# design_1_-_fan_controller.net
KiCad netlist of a schematic drawn in EAGLE
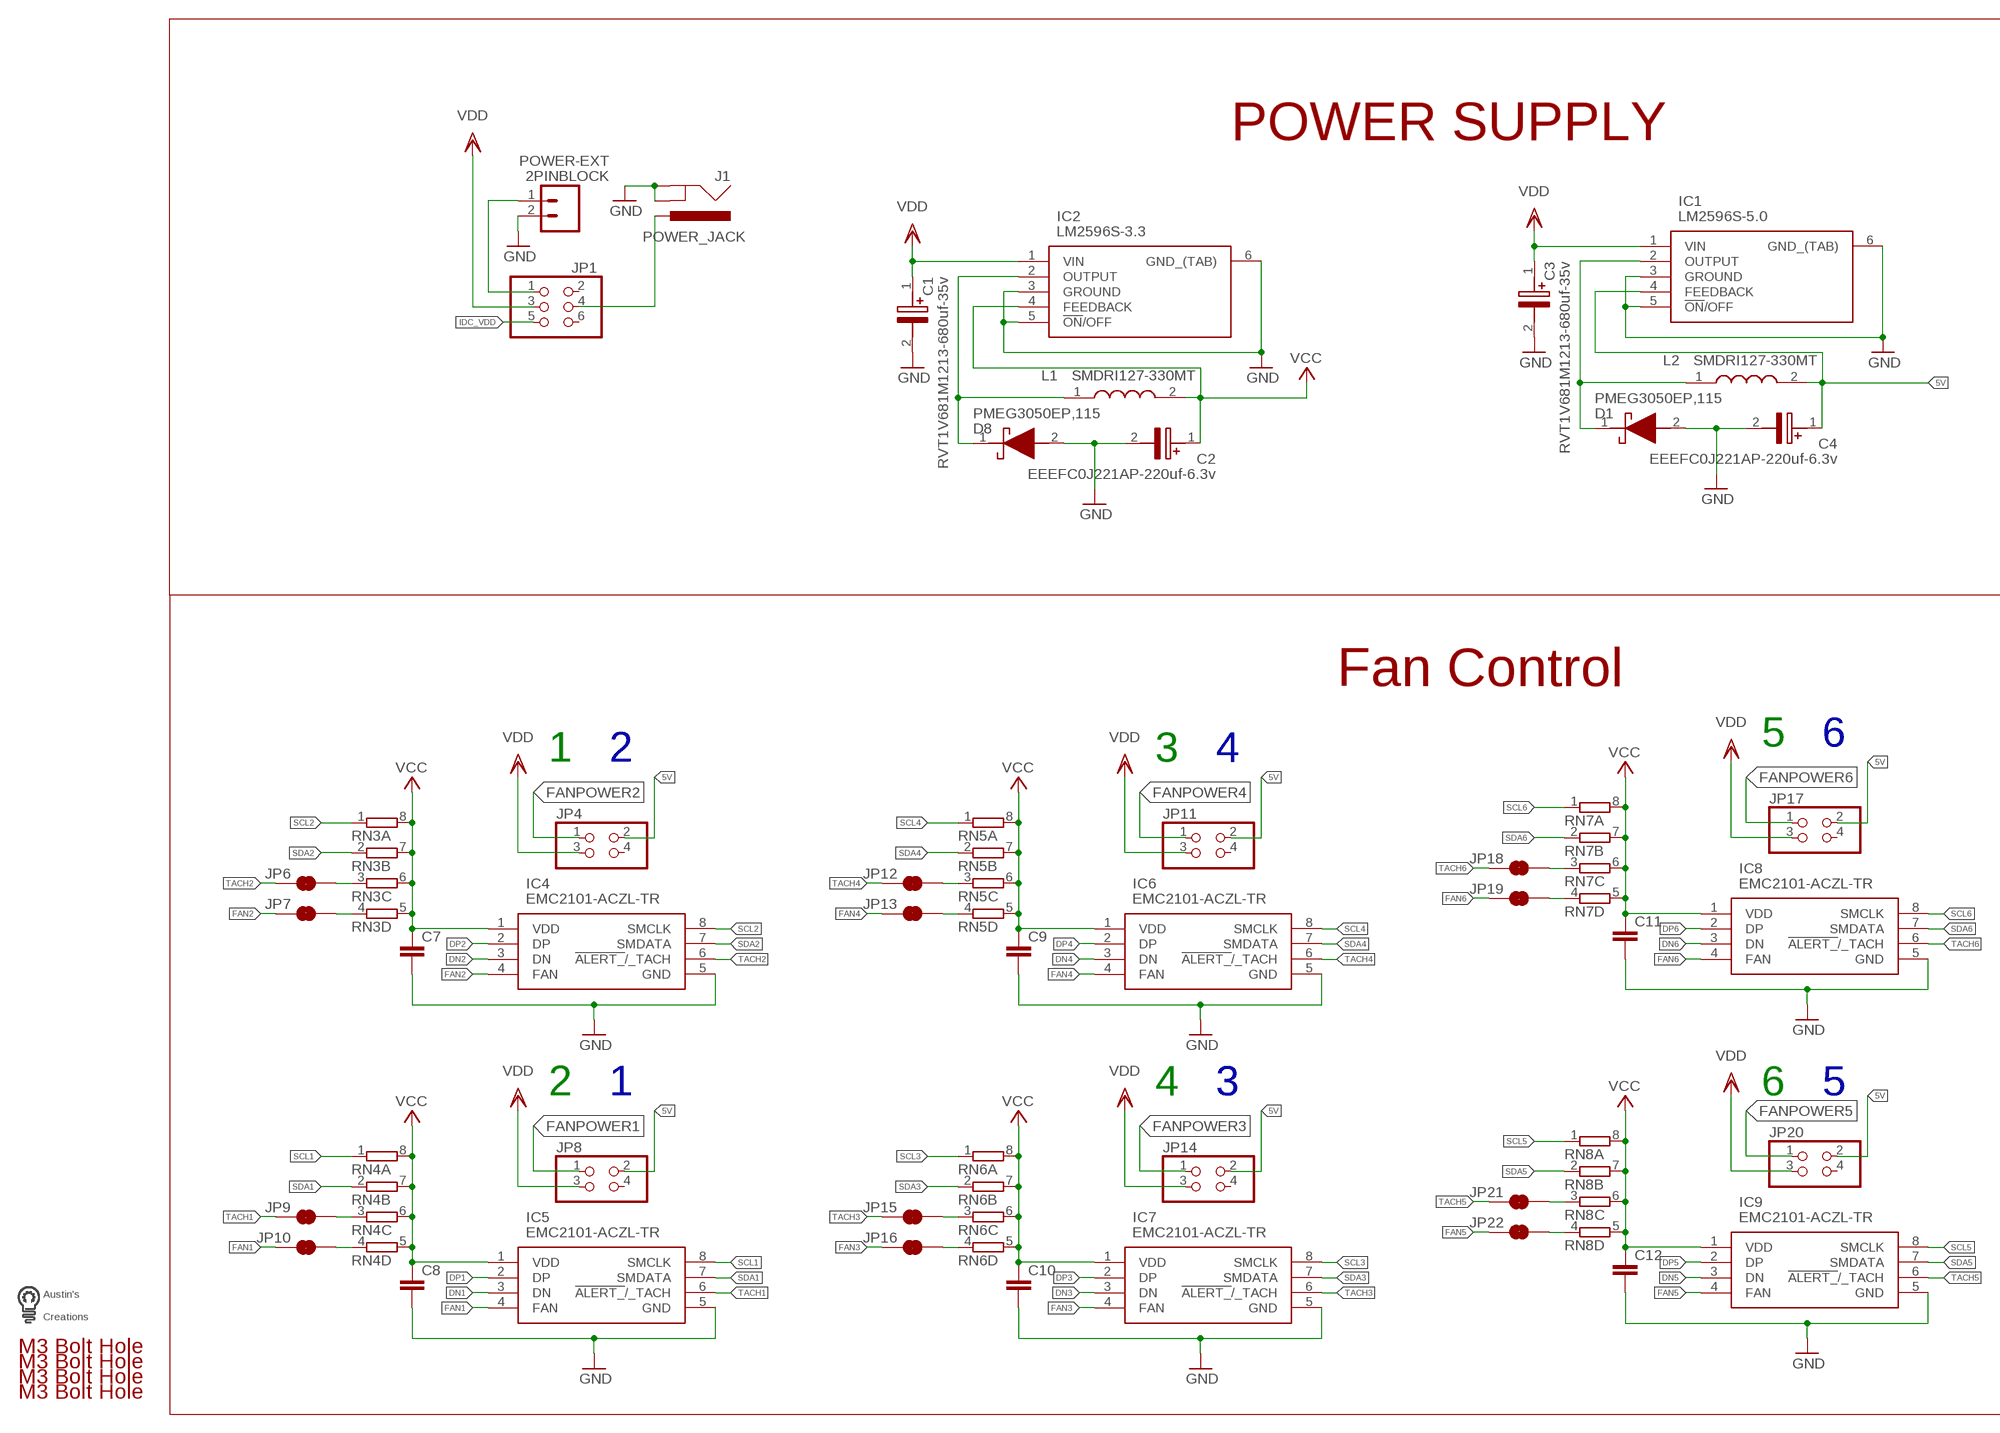
[diagram p0: schematic, sheet 1, part 1 of 2]
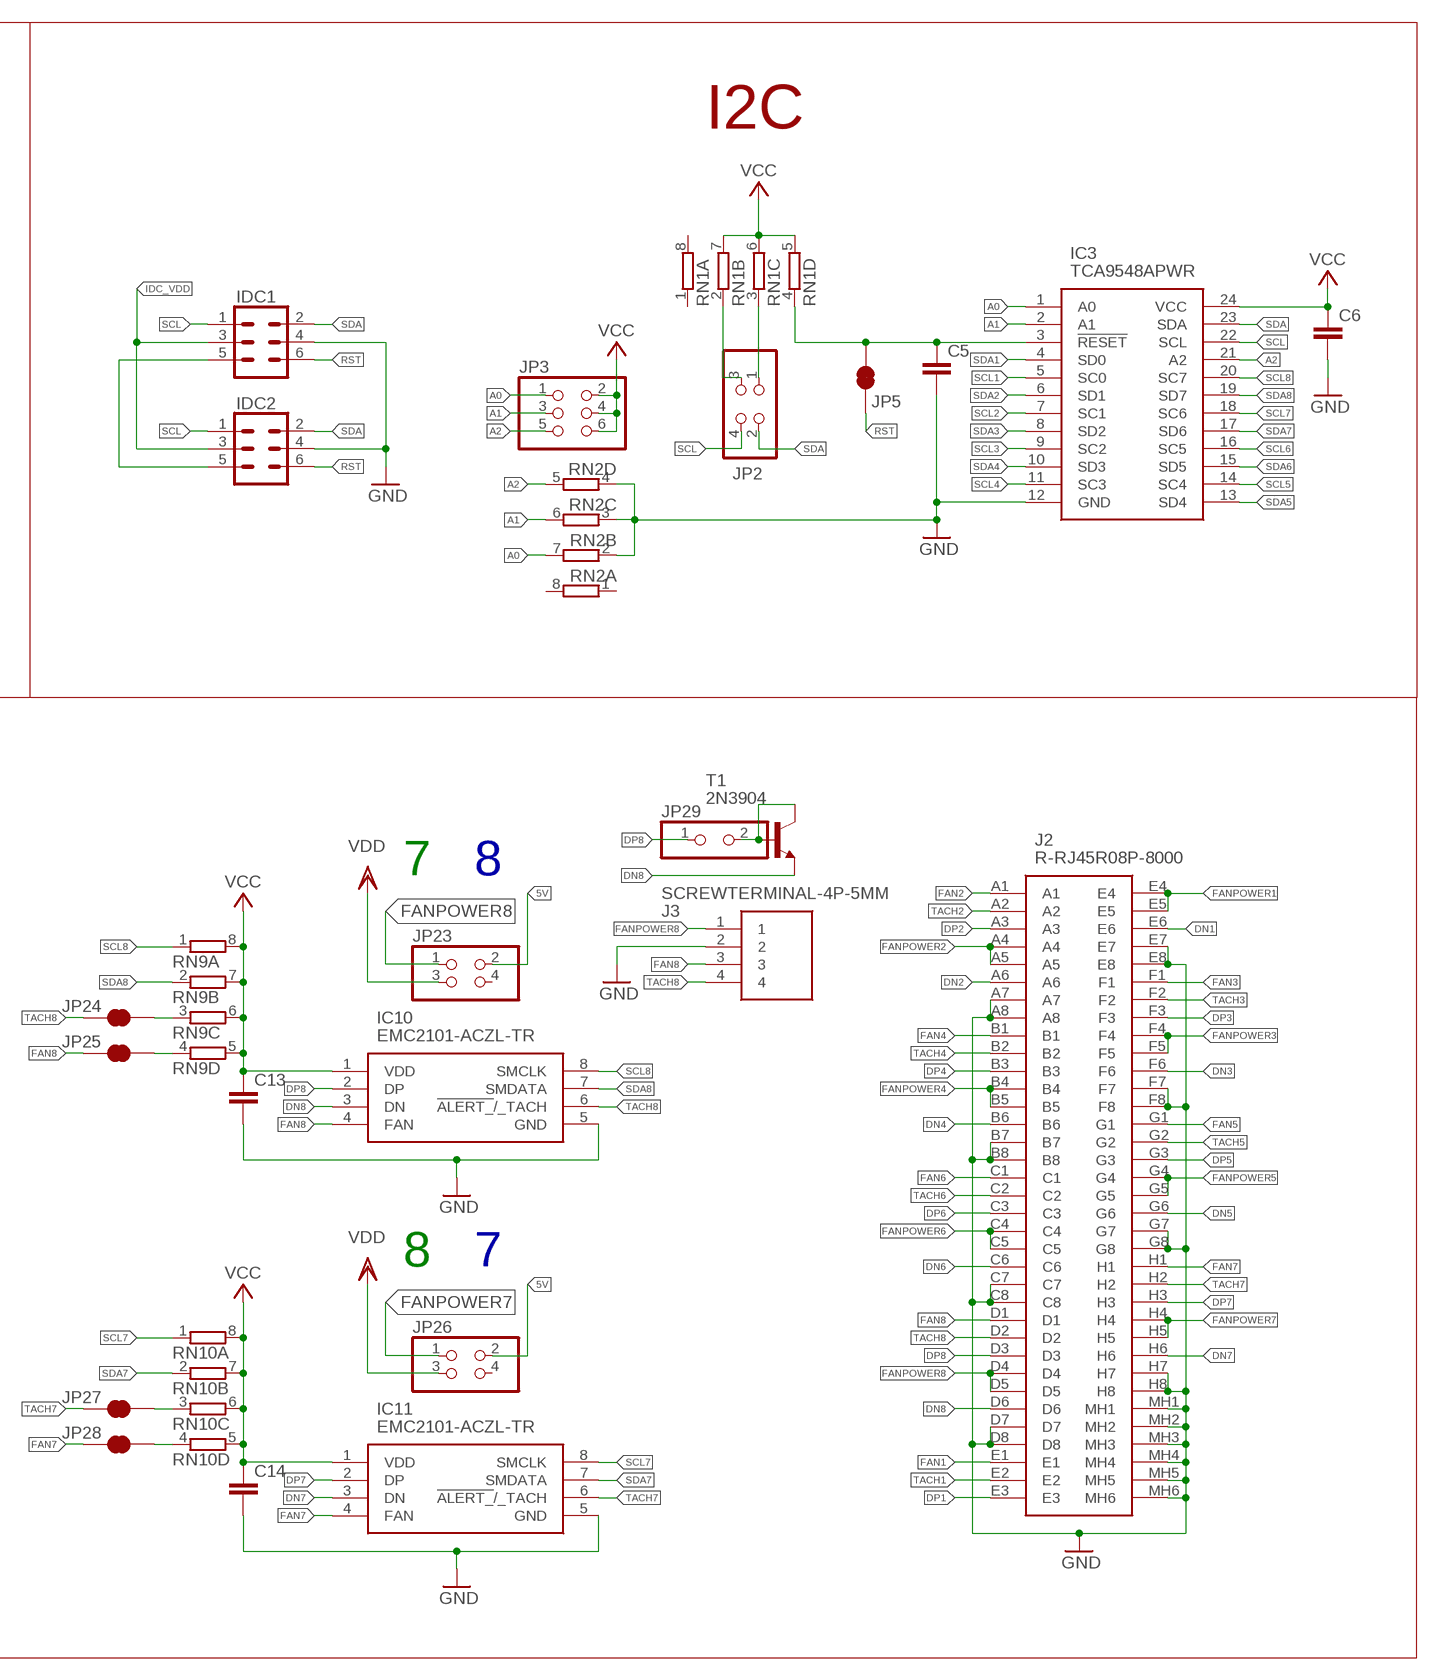
[diagram p1: schematic, sheet 1, part 2 of 2]

(export (version "E")
  (design (tool "Eeschema 10.0.6"))
  (components
    (comp (ref "C1")
      (value "RVT1V681M1213-680uf-35v")
      (footprint "eagle-import:CAPAE1350X1400N")
      (fields
        (field (name "MANUFACTURER_PART_NUMBER") "EEE-HD1V681AQ")
        (field (name "MOUSER_PART_NUMBER") "667-EEE-HD1V681AQ")
      )
      (libsource (lib "eagle-import") (part "EEE-HD1V681AQ"))
    )
    (comp (ref "C2")
      (value "EEEFC0J221AP-220uf-6.3v")
      (footprint "eagle-import:CAPAE830X650N")
      (fields (field (name "MANUFACTURER_PART_NUMBER") "EEEFC0J221AP"))
      (libsource (lib "eagle-import") (part "EEEFC0J221AP"))
    )
    (comp (ref "C3")
      (value "RVT1V681M1213-680uf-35v")
      (footprint "eagle-import:CAPAE1350X1400N")
      (fields
        (field (name "MANUFACTURER_PART_NUMBER") "EEE-HD1V681AQ")
        (field (name "MOUSER_PART_NUMBER") "667-EEE-HD1V681AQ")
      )
      (libsource (lib "eagle-import") (part "EEE-HD1V681AQ"))
    )
    (comp (ref "C4")
      (value "EEEFC0J221AP-220uf-6.3v")
      (footprint "eagle-import:CAPAE830X650N")
      (fields (field (name "MANUFACTURER_PART_NUMBER") "EEEFC0J221AP"))
      (libsource (lib "eagle-import") (part "EEEFC0J221AP"))
    )
    (comp (ref "C5")
      (value "C-EUC0603")
      (footprint "eagle-import:C0603")
      (libsource (lib "eagle-import") (part "C-EUC0603"))
    )
    (comp (ref "C6")
      (value "C-EUC0603")
      (footprint "eagle-import:C0603")
      (libsource (lib "eagle-import") (part "C-EUC0603"))
    )
    (comp (ref "C7")
      (value "C-EUC0603")
      (footprint "eagle-import:C0603")
      (libsource (lib "eagle-import") (part "C-EUC0603"))
    )
    (comp (ref "C8")
      (value "C-EUC0603")
      (footprint "eagle-import:C0603")
      (libsource (lib "eagle-import") (part "C-EUC0603"))
    )
    (comp (ref "C9")
      (value "C-EUC0603")
      (footprint "eagle-import:C0603")
      (libsource (lib "eagle-import") (part "C-EUC0603"))
    )
    (comp (ref "C10")
      (value "C-EUC0603")
      (footprint "eagle-import:C0603")
      (libsource (lib "eagle-import") (part "C-EUC0603"))
    )
    (comp (ref "C11")
      (value "C-EUC0603")
      (footprint "eagle-import:C0603")
      (libsource (lib "eagle-import") (part "C-EUC0603"))
    )
    (comp (ref "C12")
      (value "C-EUC0603")
      (footprint "eagle-import:C0603")
      (libsource (lib "eagle-import") (part "C-EUC0603"))
    )
    (comp (ref "C13")
      (value "C-EUC0603")
      (footprint "eagle-import:C0603")
      (libsource (lib "eagle-import") (part "C-EUC0603"))
    )
    (comp (ref "C14")
      (value "C-EUC0603")
      (footprint "eagle-import:C0603")
      (libsource (lib "eagle-import") (part "C-EUC0603"))
    )
    (comp (ref "D1")
      (value "PMEG3050EP,115")
      (footprint "eagle-import:PMEG3050EP115")
      (fields (field (name "MOUSER_PART_NUMBER") "771-PMEG3050EP115"))
      (libsource (lib "eagle-import") (part "PMEG3050EP,115"))
    )
    (comp (ref "D8")
      (value "PMEG3050EP,115")
      (footprint "eagle-import:PMEG3050EP115")
      (fields (field (name "MOUSER_PART_NUMBER") "771-PMEG3050EP115"))
      (libsource (lib "eagle-import") (part "PMEG3050EP,115"))
    )
    (comp (ref "IC1")
      (value "LM2596S-5.0")
      (footprint "eagle-import:TO170P1435X465-6N")
      (fields
        (field (name "MANUFACTURER_PART_NUMBER") "LM2596S-3.3/NOPB")
        (field (name "MOUSER_PART_NUMBER") "926-LM2596S-3.3/NOPB")
      )
      (libsource (lib "eagle-import") (part "LM2596S-3.3_NOPB"))
    )
    (comp (ref "IC2")
      (value "LM2596S-3.3")
      (footprint "eagle-import:TO170P1435X465-6N")
      (fields
        (field (name "MANUFACTURER_PART_NUMBER") "LM2596S-3.3/NOPB")
        (field (name "MOUSER_PART_NUMBER") "926-LM2596S-3.3/NOPB")
      )
      (libsource (lib "eagle-import") (part "LM2596S-3.3_NOPB"))
    )
    (comp (ref "IC3")
      (value "TCA9548APWR")
      (footprint "eagle-import:SOP65P640X120-24N")
      (fields (field (name "MOUSER_PART_NUMBER") "595-TCA9548APWR"))
      (libsource (lib "eagle-import") (part "TCA9548APWR"))
    )
    (comp (ref "IC4")
      (value "EMC2101-ACZL-TR")
      (footprint "eagle-import:SOP65P490X110-8N")
      (fields (field (name "MOUSER_PART_NUMBER") "886-EMC2101-ACZL-TR"))
      (libsource (lib "eagle-import") (part "EMC2101-ACZL-TR"))
    )
    (comp (ref "IC5")
      (value "EMC2101-ACZL-TR")
      (footprint "eagle-import:SOP65P490X110-8N")
      (fields (field (name "MOUSER_PART_NUMBER") "886-EMC2101-ACZL-TR"))
      (libsource (lib "eagle-import") (part "EMC2101-ACZL-TR"))
    )
    (comp (ref "IC6")
      (value "EMC2101-ACZL-TR")
      (footprint "eagle-import:SOP65P490X110-8N")
      (fields (field (name "MOUSER_PART_NUMBER") "886-EMC2101-ACZL-TR"))
      (libsource (lib "eagle-import") (part "EMC2101-ACZL-TR"))
    )
    (comp (ref "IC7")
      (value "EMC2101-ACZL-TR")
      (footprint "eagle-import:SOP65P490X110-8N")
      (fields (field (name "MOUSER_PART_NUMBER") "886-EMC2101-ACZL-TR"))
      (libsource (lib "eagle-import") (part "EMC2101-ACZL-TR"))
    )
    (comp (ref "IC8")
      (value "EMC2101-ACZL-TR")
      (footprint "eagle-import:SOP65P490X110-8N")
      (fields (field (name "MOUSER_PART_NUMBER") "886-EMC2101-ACZL-TR"))
      (libsource (lib "eagle-import") (part "EMC2101-ACZL-TR"))
    )
    (comp (ref "IC9")
      (value "EMC2101-ACZL-TR")
      (footprint "eagle-import:SOP65P490X110-8N")
      (fields (field (name "MOUSER_PART_NUMBER") "886-EMC2101-ACZL-TR"))
      (libsource (lib "eagle-import") (part "EMC2101-ACZL-TR"))
    )
    (comp (ref "IC10")
      (value "EMC2101-ACZL-TR")
      (footprint "eagle-import:SOP65P490X110-8N")
      (fields (field (name "MOUSER_PART_NUMBER") "886-EMC2101-ACZL-TR"))
      (libsource (lib "eagle-import") (part "EMC2101-ACZL-TR"))
    )
    (comp (ref "IC11")
      (value "EMC2101-ACZL-TR")
      (footprint "eagle-import:SOP65P490X110-8N")
      (fields (field (name "MOUSER_PART_NUMBER") "886-EMC2101-ACZL-TR"))
      (libsource (lib "eagle-import") (part "EMC2101-ACZL-TR"))
    )
    (comp (ref "IDC1")
      (value "CONN_03X2SHROUD")
      (footprint "eagle-import:2X3-SHROUDED")
      (libsource (lib "eagle-import") (part "CONN_03X2SHROUD"))
    )
    (comp (ref "IDC2")
      (value "CONN_03X2SHROUD")
      (footprint "eagle-import:2X3-SHROUDED")
      (libsource (lib "eagle-import") (part "CONN_03X2SHROUD"))
    )
    (comp (ref "J1")
      (value "POWER_JACK")
      (footprint "eagle-import:POWER_JACK_PTH")
      (libsource (lib "eagle-import") (part "POWER_JACK"))
    )
    (comp (ref "J2")
      (value "R-RJ45R08P-8000")
      (footprint "eagle-import:RRJ45R08P8000")
      (libsource (lib "eagle-import") (part "R-RJ45R08P-8000"))
    )
    (comp (ref "J3")
      (value "SCREWTERMINAL-4P-5MM")
      (footprint "eagle-import:SCREWTERMINAL-4P-5MM")
      (fields
        (field (name "MANUFACTURER_PART_NUMBER") "TB001-500-04BE")
        (field (name "MOUSER_PART_NUMBER") "490-TB001-500-04BE")
      )
      (libsource (lib "eagle-import") (part "SCREWTERMINAL-4P-5MM"))
    )
    (comp (ref "JP1")
      (value "PINHD-2X3")
      (footprint "eagle-import:2X03")
      (libsource (lib "eagle-import") (part "PINHD-2X3"))
    )
    (comp (ref "JP2")
      (value "PINHD-2X2")
      (footprint "eagle-import:2X02")
      (libsource (lib "eagle-import") (part "PINHD-2X2"))
    )
    (comp (ref "JP3")
      (value "PINHD-2X3")
      (footprint "eagle-import:2X03")
      (libsource (lib "eagle-import") (part "PINHD-2X3"))
    )
    (comp (ref "JP4")
      (value "PINHD-2X2")
      (footprint "eagle-import:2X02")
      (libsource (lib "eagle-import") (part "PINHD-2X2"))
    )
    (comp (ref "JP5")
      (value "JUMPER-SMT_2_NC_TRACE_SILK")
      (footprint "eagle-import:SMT-JUMPER_2_NC_TRACE_SILK")
      (libsource (lib "eagle-import") (part "JUMPER-SMT_2_NC_TRACE_SILK"))
    )
    (comp (ref "JP6")
      (value "JUMPER-SMT_2_NC_TRACE_SILK")
      (footprint "eagle-import:SMT-JUMPER_2_NC_TRACE_SILK")
      (libsource (lib "eagle-import") (part "JUMPER-SMT_2_NC_TRACE_SILK"))
    )
    (comp (ref "JP7")
      (value "JUMPER-SMT_2_NC_TRACE_SILK")
      (footprint "eagle-import:SMT-JUMPER_2_NC_TRACE_SILK")
      (libsource (lib "eagle-import") (part "JUMPER-SMT_2_NC_TRACE_SILK"))
    )
    (comp (ref "JP8")
      (value "PINHD-2X2")
      (footprint "eagle-import:2X02")
      (libsource (lib "eagle-import") (part "PINHD-2X2"))
    )
    (comp (ref "JP9")
      (value "JUMPER-SMT_2_NC_TRACE_SILK")
      (footprint "eagle-import:SMT-JUMPER_2_NC_TRACE_SILK")
      (libsource (lib "eagle-import") (part "JUMPER-SMT_2_NC_TRACE_SILK"))
    )
    (comp (ref "JP10")
      (value "JUMPER-SMT_2_NC_TRACE_SILK")
      (footprint "eagle-import:SMT-JUMPER_2_NC_TRACE_SILK")
      (libsource (lib "eagle-import") (part "JUMPER-SMT_2_NC_TRACE_SILK"))
    )
    (comp (ref "JP11")
      (value "PINHD-2X2")
      (footprint "eagle-import:2X02")
      (libsource (lib "eagle-import") (part "PINHD-2X2"))
    )
    (comp (ref "JP12")
      (value "JUMPER-SMT_2_NC_TRACE_SILK")
      (footprint "eagle-import:SMT-JUMPER_2_NC_TRACE_SILK")
      (libsource (lib "eagle-import") (part "JUMPER-SMT_2_NC_TRACE_SILK"))
    )
    (comp (ref "JP13")
      (value "JUMPER-SMT_2_NC_TRACE_SILK")
      (footprint "eagle-import:SMT-JUMPER_2_NC_TRACE_SILK")
      (libsource (lib "eagle-import") (part "JUMPER-SMT_2_NC_TRACE_SILK"))
    )
    (comp (ref "JP14")
      (value "PINHD-2X2")
      (footprint "eagle-import:2X02")
      (libsource (lib "eagle-import") (part "PINHD-2X2"))
    )
    (comp (ref "JP15")
      (value "JUMPER-SMT_2_NC_TRACE_SILK")
      (footprint "eagle-import:SMT-JUMPER_2_NC_TRACE_SILK")
      (libsource (lib "eagle-import") (part "JUMPER-SMT_2_NC_TRACE_SILK"))
    )
    (comp (ref "JP16")
      (value "JUMPER-SMT_2_NC_TRACE_SILK")
      (footprint "eagle-import:SMT-JUMPER_2_NC_TRACE_SILK")
      (libsource (lib "eagle-import") (part "JUMPER-SMT_2_NC_TRACE_SILK"))
    )
    (comp (ref "JP17")
      (value "PINHD-2X2")
      (footprint "eagle-import:2X02")
      (libsource (lib "eagle-import") (part "PINHD-2X2"))
    )
    (comp (ref "JP18")
      (value "JUMPER-SMT_2_NC_TRACE_SILK")
      (footprint "eagle-import:SMT-JUMPER_2_NC_TRACE_SILK")
      (libsource (lib "eagle-import") (part "JUMPER-SMT_2_NC_TRACE_SILK"))
    )
    (comp (ref "JP19")
      (value "JUMPER-SMT_2_NC_TRACE_SILK")
      (footprint "eagle-import:SMT-JUMPER_2_NC_TRACE_SILK")
      (libsource (lib "eagle-import") (part "JUMPER-SMT_2_NC_TRACE_SILK"))
    )
    (comp (ref "JP20")
      (value "PINHD-2X2")
      (footprint "eagle-import:2X02")
      (libsource (lib "eagle-import") (part "PINHD-2X2"))
    )
    (comp (ref "JP21")
      (value "JUMPER-SMT_2_NC_TRACE_SILK")
      (footprint "eagle-import:SMT-JUMPER_2_NC_TRACE_SILK")
      (libsource (lib "eagle-import") (part "JUMPER-SMT_2_NC_TRACE_SILK"))
    )
    (comp (ref "JP22")
      (value "JUMPER-SMT_2_NC_TRACE_SILK")
      (footprint "eagle-import:SMT-JUMPER_2_NC_TRACE_SILK")
      (libsource (lib "eagle-import") (part "JUMPER-SMT_2_NC_TRACE_SILK"))
    )
    (comp (ref "JP23")
      (value "PINHD-2X2")
      (footprint "eagle-import:2X02")
      (libsource (lib "eagle-import") (part "PINHD-2X2"))
    )
    (comp (ref "JP24")
      (value "JUMPER-SMT_2_NC_TRACE_SILK")
      (footprint "eagle-import:SMT-JUMPER_2_NC_TRACE_SILK")
      (libsource (lib "eagle-import") (part "JUMPER-SMT_2_NC_TRACE_SILK"))
    )
    (comp (ref "JP25")
      (value "JUMPER-SMT_2_NC_TRACE_SILK")
      (footprint "eagle-import:SMT-JUMPER_2_NC_TRACE_SILK")
      (libsource (lib "eagle-import") (part "JUMPER-SMT_2_NC_TRACE_SILK"))
    )
    (comp (ref "JP26")
      (value "PINHD-2X2")
      (footprint "eagle-import:2X02")
      (libsource (lib "eagle-import") (part "PINHD-2X2"))
    )
    (comp (ref "JP27")
      (value "JUMPER-SMT_2_NC_TRACE_SILK")
      (footprint "eagle-import:SMT-JUMPER_2_NC_TRACE_SILK")
      (libsource (lib "eagle-import") (part "JUMPER-SMT_2_NC_TRACE_SILK"))
    )
    (comp (ref "JP28")
      (value "JUMPER-SMT_2_NC_TRACE_SILK")
      (footprint "eagle-import:SMT-JUMPER_2_NC_TRACE_SILK")
      (libsource (lib "eagle-import") (part "JUMPER-SMT_2_NC_TRACE_SILK"))
    )
    (comp (ref "JP29")
      (value "PINHD-1X2")
      (footprint "eagle-import:1X02")
      (libsource (lib "eagle-import") (part "PINHD-1X2"))
    )
    (comp (ref "L1")
      (value "SMDRI127-330MT")
      (footprint "eagle-import:INDPM120120X800N")
      (fields
        (field (name "MANUFACTURER_PART_NUMBER") "CDRH127/LDNP-330MC")
        (field (name "MOUSER_PART_NUMBER") "851-CDRH127LDNP330MC")
      )
      (libsource (lib "eagle-import") (part "CDRH127_LDNP-330MC"))
    )
    (comp (ref "L2")
      (value "SMDRI127-330MT")
      (footprint "eagle-import:INDPM120120X800N")
      (fields
        (field (name "MANUFACTURER_PART_NUMBER") "CDRH127/LDNP-330MC")
        (field (name "MOUSER_PART_NUMBER") "851-CDRH127LDNP330MC")
      )
      (libsource (lib "eagle-import") (part "CDRH127_LDNP-330MC"))
    )
    (comp (ref "POWER-EXT")
      (value "2PINBLOCK")
      (footprint "eagle-import:SCREWTERMINAL-5MM-2")
      (libsource (lib "eagle-import") (part "2PINBLOCK"))
    )
    (comp (ref "RN1")
      (value "4R-N0603-ARC")
      (footprint "eagle-import:0603-ARC")
      (libsource (lib "eagle-import") (part "4R-N0603-ARC"))
    )
    (comp (ref "RN2")
      (value "4R-N0603-ARC")
      (footprint "eagle-import:0603-ARC")
      (libsource (lib "eagle-import") (part "4R-N0603-ARC"))
    )
    (comp (ref "RN3")
      (value "4R-N0603-ARC")
      (footprint "eagle-import:0603-ARC")
      (libsource (lib "eagle-import") (part "4R-N0603-ARC"))
    )
    (comp (ref "RN4")
      (value "4R-N0603-ARC")
      (footprint "eagle-import:0603-ARC")
      (libsource (lib "eagle-import") (part "4R-N0603-ARC"))
    )
    (comp (ref "RN5")
      (value "4R-N0603-ARC")
      (footprint "eagle-import:0603-ARC")
      (libsource (lib "eagle-import") (part "4R-N0603-ARC"))
    )
    (comp (ref "RN6")
      (value "4R-N0603-ARC")
      (footprint "eagle-import:0603-ARC")
      (libsource (lib "eagle-import") (part "4R-N0603-ARC"))
    )
    (comp (ref "RN7")
      (value "4R-N0603-ARC")
      (footprint "eagle-import:0603-ARC")
      (libsource (lib "eagle-import") (part "4R-N0603-ARC"))
    )
    (comp (ref "RN8")
      (value "4R-N0603-ARC")
      (footprint "eagle-import:0603-ARC")
      (libsource (lib "eagle-import") (part "4R-N0603-ARC"))
    )
    (comp (ref "RN9")
      (value "4R-N0603-ARC")
      (footprint "eagle-import:0603-ARC")
      (libsource (lib "eagle-import") (part "4R-N0603-ARC"))
    )
    (comp (ref "RN10")
      (value "4R-N0603-ARC")
      (footprint "eagle-import:0603-ARC")
      (libsource (lib "eagle-import") (part "4R-N0603-ARC"))
    )
    (comp (ref "T1")
      (value "2N3904")
      (footprint "eagle-import:TO92")
      (libsource (lib "eagle-import") (part "2N3904"))
    )
    (comp (ref "U$1")
      (value "M3BOLTHOLE")
      (footprint "eagle-import:M3BOLTHOLE")
      (libsource (lib "eagle-import") (part "M3BOLTHOLE"))
    )
    (comp (ref "U$2")
      (value "M3BOLTHOLE")
      (footprint "eagle-import:M3BOLTHOLE")
      (libsource (lib "eagle-import") (part "M3BOLTHOLE"))
    )
    (comp (ref "U$3")
      (value "M3BOLTHOLE")
      (footprint "eagle-import:M3BOLTHOLE")
      (libsource (lib "eagle-import") (part "M3BOLTHOLE"))
    )
    (comp (ref "U$4")
      (value "M3BOLTHOLE")
      (footprint "eagle-import:M3BOLTHOLE")
      (libsource (lib "eagle-import") (part "M3BOLTHOLE"))
    )
    (comp (ref "U$5")
      (value "LOGOMED")
      (footprint "eagle-import:LOGOMED")
      (libsource (lib "eagle-import") (part "LOGOMED"))
    )
  )
  (nets
    (net (code "1") (name "5V") (class "Default")
      (node (ref "C4") (pin "1") (pinfunction "+_1") (pintype "bidirectional"))
      (node (ref "IC1") (pin "4") (pinfunction "FEEDBACK_4") (pintype "bidirectional"))
      (node (ref "JP11") (pin "2") (pinfunction "2_2") (pintype "passive"))
      (node (ref "JP14") (pin "2") (pinfunction "2_2") (pintype "passive"))
      (node (ref "JP17") (pin "2") (pinfunction "2_2") (pintype "passive"))
      (node (ref "JP20") (pin "2") (pinfunction "2_2") (pintype "passive"))
      (node (ref "JP23") (pin "2") (pinfunction "2_2") (pintype "passive"))
      (node (ref "JP26") (pin "2") (pinfunction "2_2") (pintype "passive"))
      (node (ref "JP4") (pin "2") (pinfunction "2_2") (pintype "passive"))
      (node (ref "JP8") (pin "2") (pinfunction "2_2") (pintype "passive"))
      (node (ref "L2") (pin "2") (pinfunction "2_2") (pintype "bidirectional"))
    )
    (net (code "2") (name "A0") (class "Default")
      (node (ref "IC3") (pin "1") (pinfunction "A0_1") (pintype "bidirectional"))
      (node (ref "JP3") (pin "1") (pinfunction "1_1") (pintype "passive"))
      (node (ref "RN2") (pin "7") (pinfunction "2_7") (pintype "passive"))
    )
    (net (code "3") (name "A1") (class "Default")
      (node (ref "IC3") (pin "2") (pinfunction "A1_2") (pintype "bidirectional"))
      (node (ref "JP3") (pin "3") (pinfunction "3_3") (pintype "passive"))
      (node (ref "RN2") (pin "6") (pinfunction "2_6") (pintype "passive"))
    )
    (net (code "4") (name "A2") (class "Default")
      (node (ref "IC3") (pin "21") (pinfunction "A2_21") (pintype "bidirectional"))
      (node (ref "JP3") (pin "5") (pinfunction "5_5") (pintype "passive"))
      (node (ref "RN2") (pin "5") (pinfunction "2_5") (pintype "passive"))
    )
    (net (code "5") (name "DN1") (class "Default")
      (node (ref "IC5") (pin "3") (pinfunction "DN_3") (pintype "input"))
      (node (ref "J2") (pin "E6") (pinfunction "E6_E6") (pintype "bidirectional"))
    )
    (net (code "6") (name "DN2") (class "Default")
      (node (ref "IC4") (pin "3") (pinfunction "DN_3") (pintype "input"))
      (node (ref "J2") (pin "A6") (pinfunction "A6_A6") (pintype "bidirectional"))
    )
    (net (code "7") (name "DN3") (class "Default")
      (node (ref "IC7") (pin "3") (pinfunction "DN_3") (pintype "input"))
      (node (ref "J2") (pin "F6") (pinfunction "F6_F6") (pintype "bidirectional"))
    )
    (net (code "8") (name "DN4") (class "Default")
      (node (ref "IC6") (pin "3") (pinfunction "DN_3") (pintype "input"))
      (node (ref "J2") (pin "B6") (pinfunction "B6_B6") (pintype "bidirectional"))
    )
    (net (code "9") (name "DN5") (class "Default")
      (node (ref "IC9") (pin "3") (pinfunction "DN_3") (pintype "input"))
      (node (ref "J2") (pin "G6") (pinfunction "G6_G6") (pintype "bidirectional"))
    )
    (net (code "10") (name "DN6") (class "Default")
      (node (ref "IC8") (pin "3") (pinfunction "DN_3") (pintype "input"))
      (node (ref "J2") (pin "C6") (pinfunction "C6_C6") (pintype "bidirectional"))
    )
    (net (code "11") (name "DN7") (class "Default")
      (node (ref "IC11") (pin "3") (pinfunction "DN_3") (pintype "input"))
      (node (ref "J2") (pin "H6") (pinfunction "H6_H6") (pintype "bidirectional"))
    )
    (net (code "12") (name "DN8") (class "Default")
      (node (ref "IC10") (pin "3") (pinfunction "DN_3") (pintype "input"))
      (node (ref "J2") (pin "D6") (pinfunction "D6_D6") (pintype "bidirectional"))
      (node (ref "T1") (pin "3") (pinfunction "E_3") (pintype "passive"))
    )
    (net (code "13") (name "DP1") (class "Default")
      (node (ref "IC5") (pin "2") (pinfunction "DP_2") (pintype "input"))
      (node (ref "J2") (pin "E3") (pinfunction "E3_E3") (pintype "bidirectional"))
    )
    (net (code "14") (name "DP2") (class "Default")
      (node (ref "IC4") (pin "2") (pinfunction "DP_2") (pintype "input"))
      (node (ref "J2") (pin "A3") (pinfunction "A3_A3") (pintype "bidirectional"))
    )
    (net (code "15") (name "DP3") (class "Default")
      (node (ref "IC7") (pin "2") (pinfunction "DP_2") (pintype "input"))
      (node (ref "J2") (pin "F3") (pinfunction "F3_F3") (pintype "bidirectional"))
    )
    (net (code "16") (name "DP4") (class "Default")
      (node (ref "IC6") (pin "2") (pinfunction "DP_2") (pintype "input"))
      (node (ref "J2") (pin "B3") (pinfunction "B3_B3") (pintype "bidirectional"))
    )
    (net (code "17") (name "DP5") (class "Default")
      (node (ref "IC9") (pin "2") (pinfunction "DP_2") (pintype "input"))
      (node (ref "J2") (pin "G3") (pinfunction "G3_G3") (pintype "bidirectional"))
    )
    (net (code "18") (name "DP6") (class "Default")
      (node (ref "IC8") (pin "2") (pinfunction "DP_2") (pintype "input"))
      (node (ref "J2") (pin "C3") (pinfunction "C3_C3") (pintype "bidirectional"))
    )
    (net (code "19") (name "DP7") (class "Default")
      (node (ref "IC11") (pin "2") (pinfunction "DP_2") (pintype "input"))
      (node (ref "J2") (pin "H3") (pinfunction "H3_H3") (pintype "bidirectional"))
    )
    (net (code "20") (name "DP8") (class "Default")
      (node (ref "IC10") (pin "2") (pinfunction "DP_2") (pintype "input"))
      (node (ref "J2") (pin "D3") (pinfunction "D3_D3") (pintype "bidirectional"))
      (node (ref "JP29") (pin "1") (pinfunction "1_1") (pintype "passive"))
    )
    (net (code "21") (name "FAN1") (class "Default")
      (node (ref "IC5") (pin "4") (pinfunction "FAN_4") (pintype "output"))
      (node (ref "J2") (pin "E1") (pinfunction "E1_E1") (pintype "bidirectional"))
      (node (ref "JP10") (pin "1") (pinfunction "1_1") (pintype "passive"))
    )
    (net (code "22") (name "FAN2") (class "Default")
      (node (ref "IC4") (pin "4") (pinfunction "FAN_4") (pintype "output"))
      (node (ref "J2") (pin "A1") (pinfunction "A1_A1") (pintype "bidirectional"))
      (node (ref "JP7") (pin "1") (pinfunction "1_1") (pintype "passive"))
    )
    (net (code "23") (name "FAN3") (class "Default")
      (node (ref "IC7") (pin "4") (pinfunction "FAN_4") (pintype "output"))
      (node (ref "J2") (pin "F1") (pinfunction "F1_F1") (pintype "bidirectional"))
      (node (ref "JP16") (pin "1") (pinfunction "1_1") (pintype "passive"))
    )
    (net (code "24") (name "FAN4") (class "Default")
      (node (ref "IC6") (pin "4") (pinfunction "FAN_4") (pintype "output"))
      (node (ref "J2") (pin "B1") (pinfunction "B1_B1") (pintype "bidirectional"))
      (node (ref "JP13") (pin "1") (pinfunction "1_1") (pintype "passive"))
    )
    (net (code "25") (name "FAN5") (class "Default")
      (node (ref "IC9") (pin "4") (pinfunction "FAN_4") (pintype "output"))
      (node (ref "J2") (pin "G1") (pinfunction "G1_G1") (pintype "bidirectional"))
      (node (ref "JP22") (pin "1") (pinfunction "1_1") (pintype "passive"))
    )
    (net (code "26") (name "FAN6") (class "Default")
      (node (ref "IC8") (pin "4") (pinfunction "FAN_4") (pintype "output"))
      (node (ref "J2") (pin "C1") (pinfunction "C1_C1") (pintype "bidirectional"))
      (node (ref "JP19") (pin "1") (pinfunction "1_1") (pintype "passive"))
    )
    (net (code "27") (name "FAN7") (class "Default")
      (node (ref "IC11") (pin "4") (pinfunction "FAN_4") (pintype "output"))
      (node (ref "J2") (pin "H1") (pinfunction "H1_H1") (pintype "bidirectional"))
      (node (ref "JP28") (pin "1") (pinfunction "1_1") (pintype "passive"))
    )
    (net (code "28") (name "FAN8") (class "Default")
      (node (ref "IC10") (pin "4") (pinfunction "FAN_4") (pintype "output"))
      (node (ref "J2") (pin "D1") (pinfunction "D1_D1") (pintype "bidirectional"))
      (node (ref "J3") (pin "3") (pinfunction "3_3") (pintype "bidirectional"))
      (node (ref "JP25") (pin "1") (pinfunction "1_1") (pintype "passive"))
    )
    (net (code "29") (name "FANPOWER1") (class "Default")
      (node (ref "J2") (pin "E4") (pinfunction "E4_E4") (pintype "bidirectional"))
      (node (ref "J2") (pin "E5") (pinfunction "E5_E5") (pintype "bidirectional"))
      (node (ref "JP8") (pin "1") (pinfunction "1_1") (pintype "passive"))
    )
    (net (code "30") (name "FANPOWER2") (class "Default")
      (node (ref "J2") (pin "A4") (pinfunction "A4_A4") (pintype "bidirectional"))
      (node (ref "J2") (pin "A5") (pinfunction "A5_A5") (pintype "bidirectional"))
      (node (ref "JP4") (pin "1") (pinfunction "1_1") (pintype "passive"))
    )
    (net (code "31") (name "FANPOWER3") (class "Default")
      (node (ref "J2") (pin "F4") (pinfunction "F4_F4") (pintype "bidirectional"))
      (node (ref "J2") (pin "F5") (pinfunction "F5_F5") (pintype "bidirectional"))
      (node (ref "JP14") (pin "1") (pinfunction "1_1") (pintype "passive"))
    )
    (net (code "32") (name "FANPOWER4") (class "Default")
      (node (ref "J2") (pin "B4") (pinfunction "B4_B4") (pintype "bidirectional"))
      (node (ref "J2") (pin "B5") (pinfunction "B5_B5") (pintype "bidirectional"))
      (node (ref "JP11") (pin "1") (pinfunction "1_1") (pintype "passive"))
    )
    (net (code "33") (name "FANPOWER5") (class "Default")
      (node (ref "J2") (pin "G4") (pinfunction "G4_G4") (pintype "bidirectional"))
      (node (ref "J2") (pin "G5") (pinfunction "G5_G5") (pintype "bidirectional"))
      (node (ref "JP20") (pin "1") (pinfunction "1_1") (pintype "passive"))
    )
    (net (code "34") (name "FANPOWER6") (class "Default")
      (node (ref "J2") (pin "C4") (pinfunction "C4_C4") (pintype "bidirectional"))
      (node (ref "J2") (pin "C5") (pinfunction "C5_C5") (pintype "bidirectional"))
      (node (ref "JP17") (pin "1") (pinfunction "1_1") (pintype "passive"))
    )
    (net (code "35") (name "FANPOWER7") (class "Default")
      (node (ref "J2") (pin "H4") (pinfunction "H4_H4") (pintype "bidirectional"))
      (node (ref "J2") (pin "H5") (pinfunction "H5_H5") (pintype "bidirectional"))
      (node (ref "JP26") (pin "1") (pinfunction "1_1") (pintype "passive"))
    )
    (net (code "36") (name "FANPOWER8") (class "Default")
      (node (ref "J2") (pin "D4") (pinfunction "D4_D4") (pintype "bidirectional"))
      (node (ref "J2") (pin "D5") (pinfunction "D5_D5") (pintype "bidirectional"))
      (node (ref "J3") (pin "1") (pinfunction "1_1") (pintype "bidirectional"))
      (node (ref "JP23") (pin "1") (pinfunction "1_1") (pintype "passive"))
    )
    (net (code "37") (name "GND") (class "Default")
      (node (ref "C1") (pin "2") (pinfunction "-_2") (pintype "bidirectional"))
      (node (ref "C10") (pin "2") (pinfunction "2_2") (pintype "passive"))
      (node (ref "C11") (pin "2") (pinfunction "2_2") (pintype "passive"))
      (node (ref "C12") (pin "2") (pinfunction "2_2") (pintype "passive"))
      (node (ref "C13") (pin "2") (pinfunction "2_2") (pintype "passive"))
      (node (ref "C14") (pin "2") (pinfunction "2_2") (pintype "passive"))
      (node (ref "C2") (pin "2") (pinfunction "-_2") (pintype "bidirectional"))
      (node (ref "C3") (pin "2") (pinfunction "-_2") (pintype "bidirectional"))
      (node (ref "C4") (pin "2") (pinfunction "-_2") (pintype "bidirectional"))
      (node (ref "C5") (pin "2") (pinfunction "2_2") (pintype "passive"))
      (node (ref "C6") (pin "2") (pinfunction "2_2") (pintype "passive"))
      (node (ref "C7") (pin "2") (pinfunction "2_2") (pintype "passive"))
      (node (ref "C8") (pin "2") (pinfunction "2_2") (pintype "passive"))
      (node (ref "C9") (pin "2") (pinfunction "2_2") (pintype "passive"))
      (node (ref "D1") (pin "2") (pinfunction "A_2") (pintype "bidirectional"))
      (node (ref "D8") (pin "2") (pinfunction "A_2") (pintype "bidirectional"))
      (node (ref "IC1") (pin "3") (pinfunction "GROUND_3") (pintype "bidirectional"))
      (node (ref "IC1") (pin "5") (pinfunction "~{ON}/OFF_5") (pintype "bidirectional"))
      (node (ref "IC1") (pin "6") (pinfunction "GND_(TAB)_6") (pintype "power_in"))
      (node (ref "IC10") (pin "5") (pinfunction "GND_5") (pintype "power_in"))
      (node (ref "IC11") (pin "5") (pinfunction "GND_5") (pintype "power_in"))
      (node (ref "IC2") (pin "3") (pinfunction "GROUND_3") (pintype "bidirectional"))
      (node (ref "IC2") (pin "5") (pinfunction "~{ON}/OFF_5") (pintype "bidirectional"))
      (node (ref "IC2") (pin "6") (pinfunction "GND_(TAB)_6") (pintype "power_in"))
      (node (ref "IC3") (pin "12") (pinfunction "GND_12") (pintype "bidirectional"))
      (node (ref "IC4") (pin "5") (pinfunction "GND_5") (pintype "power_in"))
      (node (ref "IC5") (pin "5") (pinfunction "GND_5") (pintype "power_in"))
      (node (ref "IC6") (pin "5") (pinfunction "GND_5") (pintype "power_in"))
      (node (ref "IC7") (pin "5") (pinfunction "GND_5") (pintype "power_in"))
      (node (ref "IC8") (pin "5") (pinfunction "GND_5") (pintype "power_in"))
      (node (ref "IC9") (pin "5") (pinfunction "GND_5") (pintype "power_in"))
      (node (ref "IDC1") (pin "4") (pinfunction "4_4") (pintype "bidirectional"))
      (node (ref "IDC2") (pin "4") (pinfunction "4_4") (pintype "bidirectional"))
      (node (ref "J1") (pin "GND") (pinfunction "GND_GND") (pintype "bidirectional"))
      (node (ref "J1") (pin "GNDBREAK") (pinfunction "GNDBREAK_GNDBREAK") (pintype "bidirectional"))
      (node (ref "J2") (pin "A7") (pinfunction "A7_A7") (pintype "bidirectional"))
      (node (ref "J2") (pin "A8") (pinfunction "A8_A8") (pintype "bidirectional"))
      (node (ref "J2") (pin "B7") (pinfunction "B7_B7") (pintype "bidirectional"))
      (node (ref "J2") (pin "B8") (pinfunction "B8_B8") (pintype "bidirectional"))
      (node (ref "J2") (pin "C7") (pinfunction "C7_C7") (pintype "bidirectional"))
      (node (ref "J2") (pin "C8") (pinfunction "C8_C8") (pintype "bidirectional"))
      (node (ref "J2") (pin "D7") (pinfunction "D7_D7") (pintype "bidirectional"))
      (node (ref "J2") (pin "D8") (pinfunction "D8_D8") (pintype "bidirectional"))
      (node (ref "J2") (pin "E7") (pinfunction "E7_E7") (pintype "bidirectional"))
      (node (ref "J2") (pin "E8") (pinfunction "E8_E8") (pintype "bidirectional"))
      (node (ref "J2") (pin "F7") (pinfunction "F7_F7") (pintype "bidirectional"))
      (node (ref "J2") (pin "F8") (pinfunction "F8_F8") (pintype "bidirectional"))
      (node (ref "J2") (pin "G7") (pinfunction "G7_G7") (pintype "bidirectional"))
      (node (ref "J2") (pin "G8") (pinfunction "G8_G8") (pintype "bidirectional"))
      (node (ref "J2") (pin "H7") (pinfunction "H7_H7") (pintype "bidirectional"))
      (node (ref "J2") (pin "H8") (pinfunction "H8_H8") (pintype "bidirectional"))
      (node (ref "J2") (pin "MH1") (pinfunction "MH1_MH1") (pintype "bidirectional"))
      (node (ref "J2") (pin "MH2") (pinfunction "MH2_MH2") (pintype "bidirectional"))
      (node (ref "J2") (pin "MH3") (pinfunction "MH3_MH3") (pintype "bidirectional"))
      (node (ref "J2") (pin "MH4") (pinfunction "MH4_MH4") (pintype "bidirectional"))
      (node (ref "J2") (pin "MH5") (pinfunction "MH5_MH5") (pintype "bidirectional"))
      (node (ref "J2") (pin "MH6") (pinfunction "MH6_MH6") (pintype "bidirectional"))
      (node (ref "J3") (pin "2") (pinfunction "2_2") (pintype "bidirectional"))
      (node (ref "POWER-EXT") (pin "2") (pinfunction "2_2") (pintype "passive"))
      (node (ref "RN2") (pin "2") (pinfunction "1_2") (pintype "passive"))
      (node (ref "RN2") (pin "3") (pinfunction "1_3") (pintype "passive"))
      (node (ref "RN2") (pin "4") (pinfunction "1_4") (pintype "passive"))
    )
    (net (code "38") (name "IDC_VDD") (class "Default")
      (node (ref "IDC1") (pin "3") (pinfunction "3_3") (pintype "bidirectional"))
      (node (ref "IDC2") (pin "3") (pinfunction "3_3") (pintype "bidirectional"))
      (node (ref "JP1") (pin "5") (pinfunction "5_5") (pintype "passive"))
    )
    (net (code "39") (name "Net-(D1-K)") (class "Default")
      (node (ref "D1") (pin "1") (pinfunction "K_1") (pintype "bidirectional"))
      (node (ref "IC1") (pin "2") (pinfunction "OUTPUT_2") (pintype "output"))
      (node (ref "L2") (pin "1") (pinfunction "1_1") (pintype "bidirectional"))
    )
    (net (code "40") (name "Net-(D8-K)") (class "Default")
      (node (ref "D8") (pin "1") (pinfunction "K_1") (pintype "bidirectional"))
      (node (ref "IC2") (pin "2") (pinfunction "OUTPUT_2") (pintype "output"))
      (node (ref "L1") (pin "1") (pinfunction "1_1") (pintype "bidirectional"))
    )
    (net (code "41") (name "Net-(IC3-~{RESET})") (class "Default")
      (node (ref "C5") (pin "1") (pinfunction "1_1") (pintype "passive"))
      (node (ref "IC3") (pin "3") (pinfunction "~{RESET}_3") (pintype "bidirectional"))
      (node (ref "JP5") (pin "2") (pinfunction "2_2") (pintype "passive"))
      (node (ref "RN1") (pin "4") (pinfunction "1_4") (pintype "passive"))
    )
    (net (code "42") (name "Net-(IDC1-Pad5)") (class "Default")
      (node (ref "IDC1") (pin "5") (pinfunction "5_5") (pintype "bidirectional"))
      (node (ref "IDC2") (pin "5") (pinfunction "5_5") (pintype "bidirectional"))
    )
    (net (code "43") (name "Net-(J1-PadPWR)") (class "Default")
      (node (ref "J1") (pin "PWR") (pinfunction "PWR_PWR") (pintype "bidirectional"))
      (node (ref "JP1") (pin "4") (pinfunction "4_4") (pintype "passive"))
    )
    (net (code "44") (name "Net-(JP1-Pad1)") (class "Default")
      (node (ref "JP1") (pin "1") (pinfunction "1_1") (pintype "passive"))
      (node (ref "POWER-EXT") (pin "1") (pinfunction "1_1") (pintype "passive"))
    )
    (net (code "45") (name "Net-(RN1B-1)") (class "Default")
      (node (ref "JP2") (pin "3") (pinfunction "3_3") (pintype "passive"))
      (node (ref "RN1") (pin "2") (pinfunction "1_2") (pintype "passive"))
    )
    (net (code "46") (name "Net-(RN1C-1)") (class "Default")
      (node (ref "JP2") (pin "1") (pinfunction "1_1") (pintype "passive"))
      (node (ref "RN1") (pin "3") (pinfunction "1_3") (pintype "passive"))
    )
    (net (code "47") (name "Net-(RN3C-1)") (class "Default")
      (node (ref "JP6") (pin "2") (pinfunction "2_2") (pintype "passive"))
      (node (ref "RN3") (pin "3") (pinfunction "1_3") (pintype "passive"))
    )
    (net (code "48") (name "Net-(RN3D-1)") (class "Default")
      (node (ref "JP7") (pin "2") (pinfunction "2_2") (pintype "passive"))
      (node (ref "RN3") (pin "4") (pinfunction "1_4") (pintype "passive"))
    )
    (net (code "49") (name "Net-(RN4C-1)") (class "Default")
      (node (ref "JP9") (pin "2") (pinfunction "2_2") (pintype "passive"))
      (node (ref "RN4") (pin "3") (pinfunction "1_3") (pintype "passive"))
    )
    (net (code "50") (name "Net-(RN4D-1)") (class "Default")
      (node (ref "JP10") (pin "2") (pinfunction "2_2") (pintype "passive"))
      (node (ref "RN4") (pin "4") (pinfunction "1_4") (pintype "passive"))
    )
    (net (code "51") (name "Net-(RN5C-1)") (class "Default")
      (node (ref "JP12") (pin "2") (pinfunction "2_2") (pintype "passive"))
      (node (ref "RN5") (pin "3") (pinfunction "1_3") (pintype "passive"))
    )
    (net (code "52") (name "Net-(RN5D-1)") (class "Default")
      (node (ref "JP13") (pin "2") (pinfunction "2_2") (pintype "passive"))
      (node (ref "RN5") (pin "4") (pinfunction "1_4") (pintype "passive"))
    )
    (net (code "53") (name "Net-(RN6C-1)") (class "Default")
      (node (ref "JP15") (pin "2") (pinfunction "2_2") (pintype "passive"))
      (node (ref "RN6") (pin "3") (pinfunction "1_3") (pintype "passive"))
    )
    (net (code "54") (name "Net-(RN6D-1)") (class "Default")
      (node (ref "JP16") (pin "2") (pinfunction "2_2") (pintype "passive"))
      (node (ref "RN6") (pin "4") (pinfunction "1_4") (pintype "passive"))
    )
    (net (code "55") (name "Net-(RN7C-1)") (class "Default")
      (node (ref "JP18") (pin "2") (pinfunction "2_2") (pintype "passive"))
      (node (ref "RN7") (pin "3") (pinfunction "1_3") (pintype "passive"))
    )
    (net (code "56") (name "Net-(RN7D-1)") (class "Default")
      (node (ref "JP19") (pin "2") (pinfunction "2_2") (pintype "passive"))
      (node (ref "RN7") (pin "4") (pinfunction "1_4") (pintype "passive"))
    )
    (net (code "57") (name "Net-(RN8C-1)") (class "Default")
      (node (ref "JP21") (pin "2") (pinfunction "2_2") (pintype "passive"))
      (node (ref "RN8") (pin "3") (pinfunction "1_3") (pintype "passive"))
    )
    (net (code "58") (name "Net-(RN8D-1)") (class "Default")
      (node (ref "JP22") (pin "2") (pinfunction "2_2") (pintype "passive"))
      (node (ref "RN8") (pin "4") (pinfunction "1_4") (pintype "passive"))
    )
    (net (code "59") (name "Net-(RN9C-1)") (class "Default")
      (node (ref "JP24") (pin "2") (pinfunction "2_2") (pintype "passive"))
      (node (ref "RN9") (pin "3") (pinfunction "1_3") (pintype "passive"))
    )
    (net (code "60") (name "Net-(RN9D-1)") (class "Default")
      (node (ref "JP25") (pin "2") (pinfunction "2_2") (pintype "passive"))
      (node (ref "RN9") (pin "4") (pinfunction "1_4") (pintype "passive"))
    )
    (net (code "61") (name "Net-(RN10C-1)") (class "Default")
      (node (ref "JP27") (pin "2") (pinfunction "2_2") (pintype "passive"))
      (node (ref "RN10") (pin "3") (pinfunction "1_3") (pintype "passive"))
    )
    (net (code "62") (name "Net-(RN10D-1)") (class "Default")
      (node (ref "JP28") (pin "2") (pinfunction "2_2") (pintype "passive"))
      (node (ref "RN10") (pin "4") (pinfunction "1_4") (pintype "passive"))
    )
    (net (code "63") (name "Net-(T1-B)") (class "Default")
      (node (ref "JP29") (pin "2") (pinfunction "2_2") (pintype "passive"))
      (node (ref "T1") (pin "1") (pinfunction "C_1") (pintype "passive"))
      (node (ref "T1") (pin "2") (pinfunction "B_2") (pintype "passive"))
    )
    (net (code "64") (name "RST") (class "Default")
      (node (ref "IDC1") (pin "6") (pinfunction "6_6") (pintype "bidirectional"))
      (node (ref "IDC2") (pin "6") (pinfunction "6_6") (pintype "bidirectional"))
      (node (ref "JP5") (pin "1") (pinfunction "1_1") (pintype "passive"))
    )
    (net (code "65") (name "SCL") (class "Default")
      (node (ref "IC3") (pin "22") (pinfunction "SCL_22") (pintype "bidirectional"))
      (node (ref "IDC1") (pin "1") (pinfunction "1_1") (pintype "bidirectional"))
      (node (ref "IDC2") (pin "1") (pinfunction "1_1") (pintype "bidirectional"))
      (node (ref "JP2") (pin "4") (pinfunction "4_4") (pintype "passive"))
    )
    (net (code "66") (name "SCL1") (class "Default")
      (node (ref "IC3") (pin "5") (pinfunction "SC0_5") (pintype "bidirectional"))
      (node (ref "IC5") (pin "8") (pinfunction "SMCLK_8") (pintype "bidirectional"))
      (node (ref "RN4") (pin "1") (pinfunction "1_1") (pintype "passive"))
    )
    (net (code "67") (name "SCL2") (class "Default")
      (node (ref "IC3") (pin "7") (pinfunction "SC1_7") (pintype "bidirectional"))
      (node (ref "IC4") (pin "8") (pinfunction "SMCLK_8") (pintype "bidirectional"))
      (node (ref "RN3") (pin "1") (pinfunction "1_1") (pintype "passive"))
    )
    (net (code "68") (name "SCL3") (class "Default")
      (node (ref "IC3") (pin "9") (pinfunction "SC2_9") (pintype "bidirectional"))
      (node (ref "IC7") (pin "8") (pinfunction "SMCLK_8") (pintype "bidirectional"))
      (node (ref "RN6") (pin "1") (pinfunction "1_1") (pintype "passive"))
    )
    (net (code "69") (name "SCL4") (class "Default")
      (node (ref "IC3") (pin "11") (pinfunction "SC3_11") (pintype "bidirectional"))
      (node (ref "IC6") (pin "8") (pinfunction "SMCLK_8") (pintype "bidirectional"))
      (node (ref "RN5") (pin "1") (pinfunction "1_1") (pintype "passive"))
    )
    (net (code "70") (name "SCL5") (class "Default")
      (node (ref "IC3") (pin "14") (pinfunction "SC4_14") (pintype "bidirectional"))
      (node (ref "IC9") (pin "8") (pinfunction "SMCLK_8") (pintype "bidirectional"))
      (node (ref "RN8") (pin "1") (pinfunction "1_1") (pintype "passive"))
    )
    (net (code "71") (name "SCL6") (class "Default")
      (node (ref "IC3") (pin "16") (pinfunction "SC5_16") (pintype "bidirectional"))
      (node (ref "IC8") (pin "8") (pinfunction "SMCLK_8") (pintype "bidirectional"))
      (node (ref "RN7") (pin "1") (pinfunction "1_1") (pintype "passive"))
    )
    (net (code "72") (name "SCL7") (class "Default")
      (node (ref "IC11") (pin "8") (pinfunction "SMCLK_8") (pintype "bidirectional"))
      (node (ref "IC3") (pin "18") (pinfunction "SC6_18") (pintype "bidirectional"))
      (node (ref "RN10") (pin "1") (pinfunction "1_1") (pintype "passive"))
    )
    (net (code "73") (name "SCL8") (class "Default")
      (node (ref "IC10") (pin "8") (pinfunction "SMCLK_8") (pintype "bidirectional"))
      (node (ref "IC3") (pin "20") (pinfunction "SC7_20") (pintype "bidirectional"))
      (node (ref "RN9") (pin "1") (pinfunction "1_1") (pintype "passive"))
    )
    (net (code "74") (name "SDA") (class "Default")
      (node (ref "IC3") (pin "23") (pinfunction "SDA_23") (pintype "bidirectional"))
      (node (ref "IDC1") (pin "2") (pinfunction "2_2") (pintype "bidirectional"))
      (node (ref "IDC2") (pin "2") (pinfunction "2_2") (pintype "bidirectional"))
      (node (ref "JP2") (pin "2") (pinfunction "2_2") (pintype "passive"))
    )
    (net (code "75") (name "SDA1") (class "Default")
      (node (ref "IC3") (pin "4") (pinfunction "SD0_4") (pintype "bidirectional"))
      (node (ref "IC5") (pin "7") (pinfunction "SMDATA_7") (pintype "bidirectional"))
      (node (ref "RN4") (pin "2") (pinfunction "1_2") (pintype "passive"))
    )
    (net (code "76") (name "SDA2") (class "Default")
      (node (ref "IC3") (pin "6") (pinfunction "SD1_6") (pintype "bidirectional"))
      (node (ref "IC4") (pin "7") (pinfunction "SMDATA_7") (pintype "bidirectional"))
      (node (ref "RN3") (pin "2") (pinfunction "1_2") (pintype "passive"))
    )
    (net (code "77") (name "SDA3") (class "Default")
      (node (ref "IC3") (pin "8") (pinfunction "SD2_8") (pintype "bidirectional"))
      (node (ref "IC7") (pin "7") (pinfunction "SMDATA_7") (pintype "bidirectional"))
      (node (ref "RN6") (pin "2") (pinfunction "1_2") (pintype "passive"))
    )
    (net (code "78") (name "SDA4") (class "Default")
      (node (ref "IC3") (pin "10") (pinfunction "SD3_10") (pintype "bidirectional"))
      (node (ref "IC6") (pin "7") (pinfunction "SMDATA_7") (pintype "bidirectional"))
      (node (ref "RN5") (pin "2") (pinfunction "1_2") (pintype "passive"))
    )
    (net (code "79") (name "SDA5") (class "Default")
      (node (ref "IC3") (pin "13") (pinfunction "SD4_13") (pintype "bidirectional"))
      (node (ref "IC9") (pin "7") (pinfunction "SMDATA_7") (pintype "bidirectional"))
      (node (ref "RN8") (pin "2") (pinfunction "1_2") (pintype "passive"))
    )
    (net (code "80") (name "SDA6") (class "Default")
      (node (ref "IC3") (pin "15") (pinfunction "SD5_15") (pintype "bidirectional"))
      (node (ref "IC8") (pin "7") (pinfunction "SMDATA_7") (pintype "bidirectional"))
      (node (ref "RN7") (pin "2") (pinfunction "1_2") (pintype "passive"))
    )
    (net (code "81") (name "SDA7") (class "Default")
      (node (ref "IC11") (pin "7") (pinfunction "SMDATA_7") (pintype "bidirectional"))
      (node (ref "IC3") (pin "17") (pinfunction "SD6_17") (pintype "bidirectional"))
      (node (ref "RN10") (pin "2") (pinfunction "1_2") (pintype "passive"))
    )
    (net (code "82") (name "SDA8") (class "Default")
      (node (ref "IC10") (pin "7") (pinfunction "SMDATA_7") (pintype "bidirectional"))
      (node (ref "IC3") (pin "19") (pinfunction "SD7_19") (pintype "bidirectional"))
      (node (ref "RN9") (pin "2") (pinfunction "1_2") (pintype "passive"))
    )
    (net (code "83") (name "TACH1") (class "Default")
      (node (ref "IC5") (pin "6") (pinfunction "~{ALERT_}/_TACH_6") (pintype "bidirectional"))
      (node (ref "J2") (pin "E2") (pinfunction "E2_E2") (pintype "bidirectional"))
      (node (ref "JP9") (pin "1") (pinfunction "1_1") (pintype "passive"))
    )
    (net (code "84") (name "TACH2") (class "Default")
      (node (ref "IC4") (pin "6") (pinfunction "~{ALERT_}/_TACH_6") (pintype "bidirectional"))
      (node (ref "J2") (pin "A2") (pinfunction "A2_A2") (pintype "bidirectional"))
      (node (ref "JP6") (pin "1") (pinfunction "1_1") (pintype "passive"))
    )
    (net (code "85") (name "TACH3") (class "Default")
      (node (ref "IC7") (pin "6") (pinfunction "~{ALERT_}/_TACH_6") (pintype "bidirectional"))
      (node (ref "J2") (pin "F2") (pinfunction "F2_F2") (pintype "bidirectional"))
      (node (ref "JP15") (pin "1") (pinfunction "1_1") (pintype "passive"))
    )
    (net (code "86") (name "TACH4") (class "Default")
      (node (ref "IC6") (pin "6") (pinfunction "~{ALERT_}/_TACH_6") (pintype "bidirectional"))
      (node (ref "J2") (pin "B2") (pinfunction "B2_B2") (pintype "bidirectional"))
      (node (ref "JP12") (pin "1") (pinfunction "1_1") (pintype "passive"))
    )
    (net (code "87") (name "TACH5") (class "Default")
      (node (ref "IC9") (pin "6") (pinfunction "~{ALERT_}/_TACH_6") (pintype "bidirectional"))
      (node (ref "J2") (pin "G2") (pinfunction "G2_G2") (pintype "bidirectional"))
      (node (ref "JP21") (pin "1") (pinfunction "1_1") (pintype "passive"))
    )
    (net (code "88") (name "TACH6") (class "Default")
      (node (ref "IC8") (pin "6") (pinfunction "~{ALERT_}/_TACH_6") (pintype "bidirectional"))
      (node (ref "J2") (pin "C2") (pinfunction "C2_C2") (pintype "bidirectional"))
      (node (ref "JP18") (pin "1") (pinfunction "1_1") (pintype "passive"))
    )
    (net (code "89") (name "TACH7") (class "Default")
      (node (ref "IC11") (pin "6") (pinfunction "~{ALERT_}/_TACH_6") (pintype "bidirectional"))
      (node (ref "J2") (pin "H2") (pinfunction "H2_H2") (pintype "bidirectional"))
      (node (ref "JP27") (pin "1") (pinfunction "1_1") (pintype "passive"))
    )
    (net (code "90") (name "TACH8") (class "Default")
      (node (ref "IC10") (pin "6") (pinfunction "~{ALERT_}/_TACH_6") (pintype "bidirectional"))
      (node (ref "J2") (pin "D2") (pinfunction "D2_D2") (pintype "bidirectional"))
      (node (ref "J3") (pin "4") (pinfunction "4_4") (pintype "bidirectional"))
      (node (ref "JP24") (pin "1") (pinfunction "1_1") (pintype "passive"))
    )
    (net (code "91") (name "VCC") (class "Default")
      (node (ref "C10") (pin "1") (pinfunction "1_1") (pintype "passive"))
      (node (ref "C11") (pin "1") (pinfunction "1_1") (pintype "passive"))
      (node (ref "C12") (pin "1") (pinfunction "1_1") (pintype "passive"))
      (node (ref "C13") (pin "1") (pinfunction "1_1") (pintype "passive"))
      (node (ref "C14") (pin "1") (pinfunction "1_1") (pintype "passive"))
      (node (ref "C2") (pin "1") (pinfunction "+_1") (pintype "bidirectional"))
      (node (ref "C6") (pin "1") (pinfunction "1_1") (pintype "passive"))
      (node (ref "C7") (pin "1") (pinfunction "1_1") (pintype "passive"))
      (node (ref "C8") (pin "1") (pinfunction "1_1") (pintype "passive"))
      (node (ref "C9") (pin "1") (pinfunction "1_1") (pintype "passive"))
      (node (ref "IC10") (pin "1") (pinfunction "VDD_1") (pintype "power_in"))
      (node (ref "IC11") (pin "1") (pinfunction "VDD_1") (pintype "power_in"))
      (node (ref "IC2") (pin "4") (pinfunction "FEEDBACK_4") (pintype "bidirectional"))
      (node (ref "IC3") (pin "24") (pinfunction "VCC_24") (pintype "bidirectional"))
      (node (ref "IC4") (pin "1") (pinfunction "VDD_1") (pintype "power_in"))
      (node (ref "IC5") (pin "1") (pinfunction "VDD_1") (pintype "power_in"))
      (node (ref "IC6") (pin "1") (pinfunction "VDD_1") (pintype "power_in"))
      (node (ref "IC7") (pin "1") (pinfunction "VDD_1") (pintype "power_in"))
      (node (ref "IC8") (pin "1") (pinfunction "VDD_1") (pintype "power_in"))
      (node (ref "IC9") (pin "1") (pinfunction "VDD_1") (pintype "power_in"))
      (node (ref "JP3") (pin "2") (pinfunction "2_2") (pintype "passive"))
      (node (ref "JP3") (pin "4") (pinfunction "4_4") (pintype "passive"))
      (node (ref "JP3") (pin "6") (pinfunction "6_6") (pintype "passive"))
      (node (ref "L1") (pin "2") (pinfunction "2_2") (pintype "bidirectional"))
      (node (ref "RN1") (pin "5") (pinfunction "2_5") (pintype "passive"))
      (node (ref "RN1") (pin "6") (pinfunction "2_6") (pintype "passive"))
      (node (ref "RN1") (pin "7") (pinfunction "2_7") (pintype "passive"))
      (node (ref "RN10") (pin "5") (pinfunction "2_5") (pintype "passive"))
      (node (ref "RN10") (pin "6") (pinfunction "2_6") (pintype "passive"))
      (node (ref "RN10") (pin "7") (pinfunction "2_7") (pintype "passive"))
      (node (ref "RN10") (pin "8") (pinfunction "2_8") (pintype "passive"))
      (node (ref "RN3") (pin "5") (pinfunction "2_5") (pintype "passive"))
      (node (ref "RN3") (pin "6") (pinfunction "2_6") (pintype "passive"))
      (node (ref "RN3") (pin "7") (pinfunction "2_7") (pintype "passive"))
      (node (ref "RN3") (pin "8") (pinfunction "2_8") (pintype "passive"))
      (node (ref "RN4") (pin "5") (pinfunction "2_5") (pintype "passive"))
      (node (ref "RN4") (pin "6") (pinfunction "2_6") (pintype "passive"))
      (node (ref "RN4") (pin "7") (pinfunction "2_7") (pintype "passive"))
      (node (ref "RN4") (pin "8") (pinfunction "2_8") (pintype "passive"))
      (node (ref "RN5") (pin "5") (pinfunction "2_5") (pintype "passive"))
      (node (ref "RN5") (pin "6") (pinfunction "2_6") (pintype "passive"))
      (node (ref "RN5") (pin "7") (pinfunction "2_7") (pintype "passive"))
      (node (ref "RN5") (pin "8") (pinfunction "2_8") (pintype "passive"))
      (node (ref "RN6") (pin "5") (pinfunction "2_5") (pintype "passive"))
      (node (ref "RN6") (pin "6") (pinfunction "2_6") (pintype "passive"))
      (node (ref "RN6") (pin "7") (pinfunction "2_7") (pintype "passive"))
      (node (ref "RN6") (pin "8") (pinfunction "2_8") (pintype "passive"))
      (node (ref "RN7") (pin "5") (pinfunction "2_5") (pintype "passive"))
      (node (ref "RN7") (pin "6") (pinfunction "2_6") (pintype "passive"))
      (node (ref "RN7") (pin "7") (pinfunction "2_7") (pintype "passive"))
      (node (ref "RN7") (pin "8") (pinfunction "2_8") (pintype "passive"))
      (node (ref "RN8") (pin "5") (pinfunction "2_5") (pintype "passive"))
      (node (ref "RN8") (pin "6") (pinfunction "2_6") (pintype "passive"))
      (node (ref "RN8") (pin "7") (pinfunction "2_7") (pintype "passive"))
      (node (ref "RN8") (pin "8") (pinfunction "2_8") (pintype "passive"))
      (node (ref "RN9") (pin "5") (pinfunction "2_5") (pintype "passive"))
      (node (ref "RN9") (pin "6") (pinfunction "2_6") (pintype "passive"))
      (node (ref "RN9") (pin "7") (pinfunction "2_7") (pintype "passive"))
      (node (ref "RN9") (pin "8") (pinfunction "2_8") (pintype "passive"))
    )
    (net (code "92") (name "VDD") (class "Default")
      (node (ref "C1") (pin "1") (pinfunction "+_1") (pintype "bidirectional"))
      (node (ref "C3") (pin "1") (pinfunction "+_1") (pintype "bidirectional"))
      (node (ref "IC1") (pin "1") (pinfunction "VIN_1") (pintype "input"))
      (node (ref "IC2") (pin "1") (pinfunction "VIN_1") (pintype "input"))
      (node (ref "JP1") (pin "3") (pinfunction "3_3") (pintype "passive"))
      (node (ref "JP11") (pin "3") (pinfunction "3_3") (pintype "passive"))
      (node (ref "JP14") (pin "3") (pinfunction "3_3") (pintype "passive"))
      (node (ref "JP17") (pin "3") (pinfunction "3_3") (pintype "passive"))
      (node (ref "JP20") (pin "3") (pinfunction "3_3") (pintype "passive"))
      (node (ref "JP23") (pin "3") (pinfunction "3_3") (pintype "passive"))
      (node (ref "JP26") (pin "3") (pinfunction "3_3") (pintype "passive"))
      (node (ref "JP4") (pin "3") (pinfunction "3_3") (pintype "passive"))
      (node (ref "JP8") (pin "3") (pinfunction "3_3") (pintype "passive"))
    )
    (net (code "93") (name "unconnected-(JP1-Pad2)") (class "Default")
      (node (ref "JP1") (pin "2") (pinfunction "2_2") (pintype "passive"))
    )
    (net (code "94") (name "unconnected-(JP1-Pad6)") (class "Default")
      (node (ref "JP1") (pin "6") (pinfunction "6_6") (pintype "passive"))
    )
    (net (code "95") (name "unconnected-(JP4-Pad4)") (class "Default")
      (node (ref "JP4") (pin "4") (pinfunction "4_4") (pintype "passive"))
    )
    (net (code "96") (name "unconnected-(JP8-Pad4)") (class "Default")
      (node (ref "JP8") (pin "4") (pinfunction "4_4") (pintype "passive"))
    )
    (net (code "97") (name "unconnected-(JP11-Pad4)") (class "Default")
      (node (ref "JP11") (pin "4") (pinfunction "4_4") (pintype "passive"))
    )
    (net (code "98") (name "unconnected-(JP14-Pad4)") (class "Default")
      (node (ref "JP14") (pin "4") (pinfunction "4_4") (pintype "passive"))
    )
    (net (code "99") (name "unconnected-(JP17-Pad4)") (class "Default")
      (node (ref "JP17") (pin "4") (pinfunction "4_4") (pintype "passive"))
    )
    (net (code "100") (name "unconnected-(JP20-Pad4)") (class "Default")
      (node (ref "JP20") (pin "4") (pinfunction "4_4") (pintype "passive"))
    )
    (net (code "101") (name "unconnected-(JP23-Pad4)") (class "Default")
      (node (ref "JP23") (pin "4") (pinfunction "4_4") (pintype "passive"))
    )
    (net (code "102") (name "unconnected-(JP26-Pad4)") (class "Default")
      (node (ref "JP26") (pin "4") (pinfunction "4_4") (pintype "passive"))
    )
    (net (code "103") (name "unconnected-(RN1-Pad1)") (class "Default")
      (node (ref "RN1") (pin "1") (pinfunction "1_1") (pintype "passive"))
    )
    (net (code "104") (name "unconnected-(RN1A-2-Pad8)") (class "Default")
      (node (ref "RN1") (pin "8") (pinfunction "2_8") (pintype "passive"))
    )
    (net (code "105") (name "unconnected-(RN2-Pad1)") (class "Default")
      (node (ref "RN2") (pin "1") (pinfunction "1_1") (pintype "passive"))
    )
    (net (code "106") (name "unconnected-(RN2A-2-Pad8)") (class "Default")
      (node (ref "RN2") (pin "8") (pinfunction "2_8") (pintype "passive"))
    )
  )
)
